# receiver2.net
KiCad netlist of a schematic drawn in EAGLE
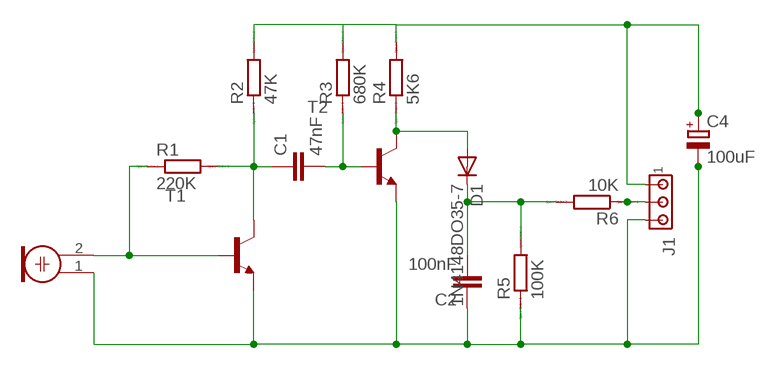
[diagram p0: schematic, sheet 1]

(export (version "E")
  (design (tool "Eeschema 10.0.6"))
  (components
    (comp (ref "C1")
      (value "47nF")
      (footprint "eagle-import:C2.5-2")
      (libsource (lib "eagle-import") (part "C2.5/2"))
    )
    (comp (ref "C2")
      (value "100nF")
      (footprint "eagle-import:C2.5-2")
      (libsource (lib "eagle-import") (part "C2.5/2"))
    )
    (comp (ref "C4")
      (value "100uF")
      (footprint "eagle-import:B45181A")
      (libsource (lib "eagle-import") (part "CPOL-EUB45181A"))
    )
    (comp (ref "D1")
      (value "1N4148DO35-7")
      (footprint "eagle-import:DO35-7")
      (libsource (lib "eagle-import") (part "1N4148DO35-7"))
    )
    (comp (ref "J1")
      (value "MTA03-100")
      (footprint "eagle-import:10X03MTA")
      (libsource (lib "eagle-import") (part "MTA03-100"))
    )
    (comp (ref "M1")
      (value "ELECTRET_MICROPHON-F6050AP")
      (footprint "eagle-import:F6050AP")
      (libsource (lib "eagle-import") (part "ELECTRET_MICROPHON-F6050AP"))
    )
    (comp (ref "R1")
      (value "220K")
      (footprint "eagle-import:0207_10")
      (libsource (lib "eagle-import") (part "R0207/10"))
    )
    (comp (ref "R2")
      (value "47K")
      (footprint "eagle-import:0207_10")
      (libsource (lib "eagle-import") (part "R0207/10"))
    )
    (comp (ref "R3")
      (value "680K")
      (footprint "eagle-import:0207_10")
      (libsource (lib "eagle-import") (part "R0207/10"))
    )
    (comp (ref "R4")
      (value "5K6")
      (footprint "eagle-import:0207_10")
      (libsource (lib "eagle-import") (part "R0207/10"))
    )
    (comp (ref "R5")
      (value "100K")
      (footprint "eagle-import:0207_10")
      (libsource (lib "eagle-import") (part "R0207/10"))
    )
    (comp (ref "R6")
      (value "10K")
      (footprint "eagle-import:0207_10")
      (libsource (lib "eagle-import") (part "R0207/10"))
    )
    (comp (ref "T1")
      (value "BC548-NPN-TO92-CBE")
      (footprint "eagle-import:TO92-CBE")
      (libsource (lib "eagle-import") (part "-NPN-TO92-CBEBC548"))
    )
    (comp (ref "T2")
      (value "BC548-NPN-TO92-CBE")
      (footprint "eagle-import:TO92-CBE")
      (libsource (lib "eagle-import") (part "-NPN-TO92-CBEBC548"))
    )
  )
  (nets
    (net (code "1") (name "Net-(C1-Pad1)") (class "Default")
      (node (ref "C1") (pin "1") (pinfunction "1_1") (pintype "passive"))
      (node (ref "R1") (pin "2") (pinfunction "2_2") (pintype "passive"))
      (node (ref "R2") (pin "1") (pinfunction "1_1") (pintype "passive"))
      (node (ref "T1") (pin "C") (pinfunction "C_C") (pintype "passive"))
    )
    (net (code "2") (name "Net-(C1-Pad2)") (class "Default")
      (node (ref "C1") (pin "2") (pinfunction "2_2") (pintype "passive"))
      (node (ref "R3") (pin "1") (pinfunction "1_1") (pintype "passive"))
      (node (ref "T2") (pin "B") (pinfunction "B_B") (pintype "passive"))
    )
    (net (code "3") (name "Net-(C2-Pad1)") (class "Default")
      (node (ref "C2") (pin "1") (pinfunction "1_1") (pintype "passive"))
      (node (ref "C4") (pin "-") (pinfunction "-_-") (pintype "passive"))
      (node (ref "J1") (pin "3") (pinfunction "3_3") (pintype "passive"))
      (node (ref "M1") (pin "1") (pinfunction "1_1") (pintype "passive"))
      (node (ref "R5") (pin "1") (pinfunction "1_1") (pintype "passive"))
      (node (ref "T1") (pin "E") (pinfunction "E_E") (pintype "passive"))
      (node (ref "T2") (pin "E") (pinfunction "E_E") (pintype "passive"))
    )
    (net (code "4") (name "Net-(C2-Pad2)") (class "Default")
      (node (ref "C2") (pin "2") (pinfunction "2_2") (pintype "passive"))
      (node (ref "D1") (pin "C") (pinfunction "C_C") (pintype "passive"))
      (node (ref "R5") (pin "2") (pinfunction "2_2") (pintype "passive"))
      (node (ref "R6") (pin "2") (pinfunction "2_2") (pintype "passive"))
    )
    (net (code "5") (name "Net-(C4-Pad+)") (class "Default")
      (node (ref "C4") (pin "+") (pinfunction "+_+") (pintype "passive"))
      (node (ref "J1") (pin "1") (pinfunction "1_1") (pintype "passive"))
      (node (ref "R2") (pin "2") (pinfunction "2_2") (pintype "passive"))
      (node (ref "R3") (pin "2") (pinfunction "2_2") (pintype "passive"))
      (node (ref "R4") (pin "2") (pinfunction "2_2") (pintype "passive"))
    )
    (net (code "6") (name "Net-(D1-PadA)") (class "Default")
      (node (ref "D1") (pin "A") (pinfunction "A_A") (pintype "passive"))
      (node (ref "R4") (pin "1") (pinfunction "1_1") (pintype "passive"))
      (node (ref "T2") (pin "C") (pinfunction "C_C") (pintype "passive"))
    )
    (net (code "7") (name "Net-(J1-Pad2)") (class "Default")
      (node (ref "J1") (pin "2") (pinfunction "2_2") (pintype "passive"))
      (node (ref "R6") (pin "1") (pinfunction "1_1") (pintype "passive"))
    )
    (net (code "8") (name "Net-(M1-Pad2)") (class "Default")
      (node (ref "M1") (pin "2") (pinfunction "2_2") (pintype "passive"))
      (node (ref "R1") (pin "1") (pinfunction "1_1") (pintype "passive"))
      (node (ref "T1") (pin "B") (pinfunction "B_B") (pintype "passive"))
    )
  )
)
